# BME280.net
KiCad netlist of a schematic drawn in Altium Designer
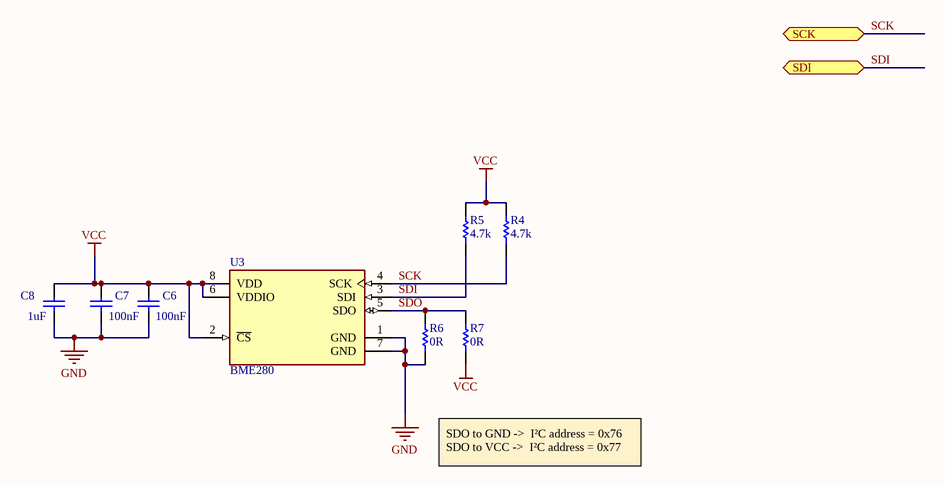
[diagram p0: BME280.SchDoc]

(export (version "E")
  (design (tool "Eeschema 10.0.6"))
  (components
    (comp (ref "C6")
      (value "100nF")
      (footprint "CAPC1005X56X25LL10T15")
      (fields
        (field (name "PART NUMBER") "0402YD104KAT2A")
        (field (name "MANUFACTURER") "AVX Interconnect / Elco")
      )
      (libsource (lib "Altium Content Vault") (part "CAP"))
    )
    (comp (ref "C7")
      (value "100nF")
      (footprint "CAPC1005X56X25LL10T15")
      (fields
        (field (name "PART NUMBER") "0402YD104KAT2A")
        (field (name "MANUFACTURER") "AVX Interconnect / Elco")
      )
      (libsource (lib "Altium Content Vault") (part "CAP"))
    )
    (comp (ref "C8")
      (value "1uF")
      (footprint "CAPC2013X145X50LL20T25")
      (fields (field (name "MANUFACTURER") "Kemet") (field (name "PART NUMBER") "C0805C105K4PACTU"))
      (libsource (lib "Altium Content Vault") (part "CAP"))
    )
    (comp (ref "R4")
      (value "4.7k")
      (footprint "RESC1005X40X25LL05T05")
      (description "Chip Resistor, 4.7 KOhm, +/- 1%, 0.1 W, -55 to 155 degC, 0402 (1005 Metric), RoHS, Tape and Reel")
      (fields (field (name "TOLERANCE") "1%") (field (name "PARTNUMBER") "ERJ-2RKF4701X"))
      (libsource (lib "Altium Content Vault") (part "RES-2"))
    )
    (comp (ref "R5")
      (value "4.7k")
      (footprint "RESC1005X40X25LL05T05")
      (description "Chip Resistor, 4.7 KOhm, +/- 1%, 0.1 W, -55 to 155 degC, 0402 (1005 Metric), RoHS, Tape and Reel")
      (fields (field (name "TOLERANCE") "1%") (field (name "PARTNUMBER") "ERJ-2RKF4701X"))
      (libsource (lib "Altium Content Vault") (part "RES-2"))
    )
    (comp (ref "R6")
      (value "0R")
      (footprint "RESC1005X40X25ML05T10")
      (fields (field (name "MANUFACTURER") "Yageo / Phycomp") (field (name "PART NUMBER") "RC0402JR-130RL"))
      (libsource (lib "Altium Content Vault") (part "RES"))
    )
    (comp (ref "R7")
      (value "0R")
      (footprint "RESC1005X40X25ML05T10")
      (fields (field (name "MANUFACTURER") "Yageo / Phycomp") (field (name "PART NUMBER") "RC0402JR-130RL"))
      (libsource (lib "Altium Content Vault") (part "RES"))
    )
    (comp (ref "U3")
      (value "BME280")
      (footprint "FP-BME280-MFG")
      (description "SENSOR PRESSURE HUMIDITY TEMP")
      (libsource (lib "Altium Content Vault") (part "0dc00059c2188b5fe1feb3ffa9c2262"))
    )
  )
  (nets
    (net (code "1") (name "/SCK") (class "Default")
      (node (ref "R4") (pin "1") (pinfunction "1_1") (pintype "passive"))
      (node (ref "U3") (pin "4") (pinfunction "SCK_4") (pintype "input"))
    )
    (net (code "2") (name "/SDI") (class "Default")
      (node (ref "R5") (pin "1") (pinfunction "1_1") (pintype "passive"))
      (node (ref "U3") (pin "3") (pinfunction "SDI_3") (pintype "input"))
    )
    (net (code "3") (name "/SDO") (class "Default")
      (node (ref "R6") (pin "2") (pinfunction "2_2") (pintype "passive"))
      (node (ref "R7") (pin "2") (pinfunction "2_2") (pintype "passive"))
      (node (ref "U3") (pin "5") (pinfunction "SDO_5") (pintype "bidirectional"))
    )
    (net (code "4") (name "GND") (class "Default")
      (node (ref "C6") (pin "2") (pinfunction "2_2") (pintype "passive"))
      (node (ref "C7") (pin "2") (pinfunction "2_2") (pintype "passive"))
      (node (ref "C8") (pin "2") (pinfunction "2_2") (pintype "passive"))
      (node (ref "R6") (pin "1") (pinfunction "1_1") (pintype "passive"))
      (node (ref "U3") (pin "1") (pinfunction "GND_1") (pintype "power_in"))
      (node (ref "U3") (pin "7") (pinfunction "GND_7") (pintype "power_in"))
    )
    (net (code "5") (name "VCC") (class "Default")
      (node (ref "C6") (pin "1") (pinfunction "1_1") (pintype "passive"))
      (node (ref "C7") (pin "1") (pinfunction "1_1") (pintype "passive"))
      (node (ref "C8") (pin "1") (pinfunction "1_1") (pintype "passive"))
      (node (ref "R4") (pin "2") (pinfunction "2_2") (pintype "passive"))
      (node (ref "R5") (pin "2") (pinfunction "2_2") (pintype "passive"))
      (node (ref "R7") (pin "1") (pinfunction "1_1") (pintype "passive"))
      (node (ref "U3") (pin "2") (pinfunction "~{CS}_2") (pintype "input"))
      (node (ref "U3") (pin "6") (pinfunction "VDDIO_6") (pintype "power_in"))
      (node (ref "U3") (pin "8") (pinfunction "VDD_8") (pintype "power_in"))
    )
  )
)
